# diagramm.net
KiCad netlist of a schematic drawn in EAGLE
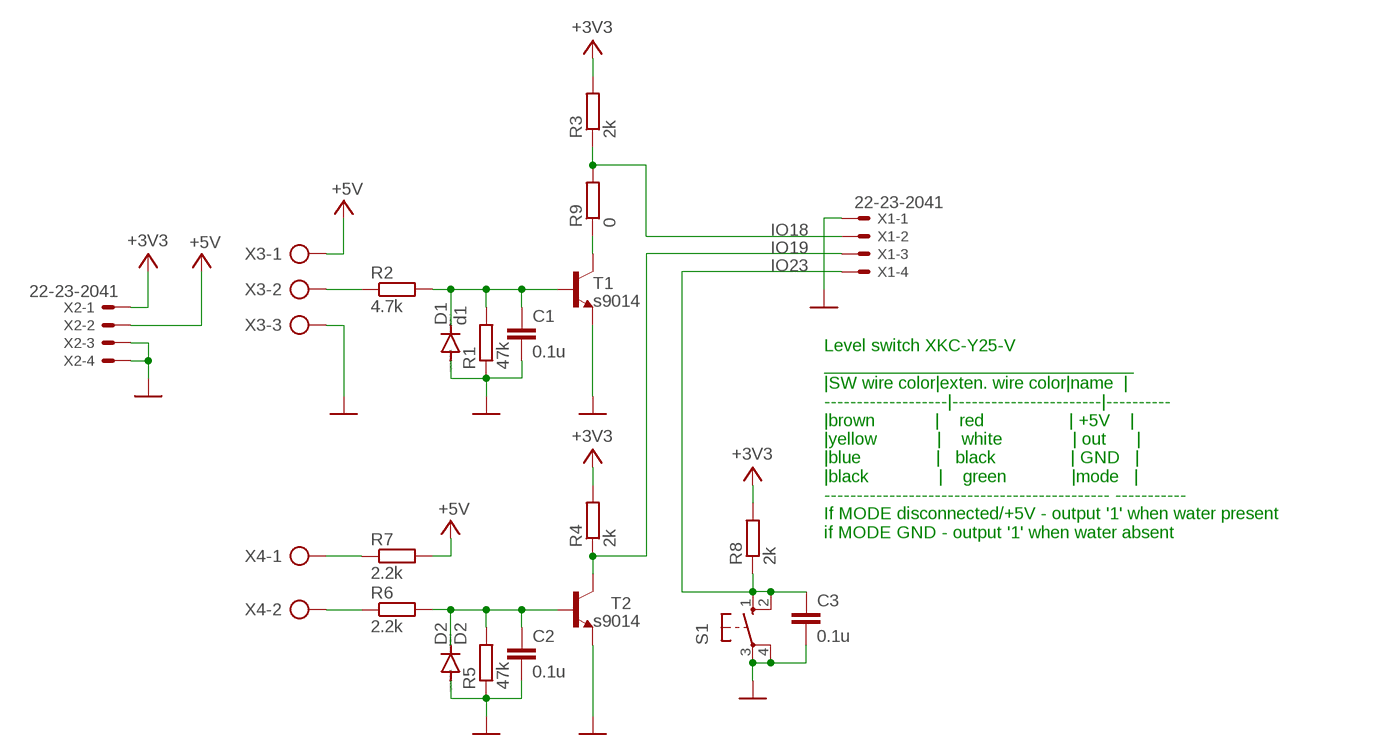
[diagram p0: schematic, sheet 1]

(export (version "E")
  (design (tool "Eeschema 10.0.6"))
  (components
    (comp (ref "C1")
      (value "0.1u")
      (footprint "eagle-import:C1206")
      (libsource (lib "eagle-import") (part "C-EUC1206"))
    )
    (comp (ref "C2")
      (value "0.1u")
      (footprint "eagle-import:C1206")
      (libsource (lib "eagle-import") (part "C-EUC1206"))
    )
    (comp (ref "C3")
      (value "0.1u")
      (footprint "eagle-import:C1206")
      (libsource (lib "eagle-import") (part "C-EUC1206"))
    )
    (comp (ref "D1")
      (value "d1")
      (footprint "eagle-import:DO214AC")
      (libsource (lib "eagle-import") (part "DIODE-DO214AC"))
    )
    (comp (ref "D2")
      (value "D2")
      (footprint "eagle-import:DO214AC")
      (libsource (lib "eagle-import") (part "DIODE-DO214AC"))
    )
    (comp (ref "R1")
      (value "47k")
      (footprint "eagle-import:R1206")
      (libsource (lib "eagle-import") (part "R-EU_R1206"))
    )
    (comp (ref "R2")
      (value "4.7k")
      (footprint "eagle-import:R1206")
      (libsource (lib "eagle-import") (part "R-EU_R1206"))
    )
    (comp (ref "R3")
      (value "2k")
      (footprint "eagle-import:R1206")
      (libsource (lib "eagle-import") (part "R-EU_R1206"))
    )
    (comp (ref "R4")
      (value "2k")
      (footprint "eagle-import:R1206")
      (libsource (lib "eagle-import") (part "R-EU_R1206"))
    )
    (comp (ref "R5")
      (value "47k")
      (footprint "eagle-import:R1206")
      (libsource (lib "eagle-import") (part "R-EU_R1206"))
    )
    (comp (ref "R6")
      (value "2.2k")
      (footprint "eagle-import:R1206")
      (libsource (lib "eagle-import") (part "R-EU_R1206"))
    )
    (comp (ref "R7")
      (value "2.2k")
      (footprint "eagle-import:R1206")
      (libsource (lib "eagle-import") (part "R-EU_R1206"))
    )
    (comp (ref "R8")
      (value "2k")
      (footprint "eagle-import:R1206")
      (libsource (lib "eagle-import") (part "R-EU_R1206"))
    )
    (comp (ref "R9")
      (value "0")
      (footprint "eagle-import:R1206")
      (libsource (lib "eagle-import") (part "R-EU_R1206"))
    )
    (comp (ref "S1")
      (value "10-XX")
      (footprint "eagle-import:B3F-10XX")
      (fields (field (name "MPN") "B3F-1000"))
      (libsource (lib "eagle-import") (part "10-XX"))
    )
    (comp (ref "T1")
      (value "s9014")
      (footprint "eagle-import:SOT23-BEC")
      (libsource (lib "eagle-import") (part "-NPN-SOT23-BECBC808"))
    )
    (comp (ref "T2")
      (value "s9014")
      (footprint "eagle-import:SOT23-BEC")
      (libsource (lib "eagle-import") (part "-NPN-SOT23-BECBC808"))
    )
    (comp (ref "X1")
      (value "22-23-2041")
      (footprint "eagle-import:22-23-2041")
      (fields (field (name "MF") "MOLEX"))
      (libsource (lib "eagle-import") (part "22-23-2041"))
    )
    (comp (ref "X2")
      (value "22-23-2041")
      (footprint "eagle-import:22-23-2041")
      (fields (field (name "MF") "MOLEX"))
      (libsource (lib "eagle-import") (part "22-23-2041"))
    )
    (comp (ref "X3")
      (value "AK300/3")
      (footprint "eagle-import:AK300_3")
      (libsource (lib "eagle-import") (part "AK300/3"))
    )
    (comp (ref "X4")
      (value "AK300/2")
      (footprint "eagle-import:AK300_2")
      (libsource (lib "eagle-import") (part "AK300/2"))
    )
  )
  (nets
    (net (code "1") (name "+3V3") (class "Default")
      (node (ref "R3") (pin "2") (pinfunction "2_2") (pintype "passive"))
      (node (ref "R4") (pin "2") (pinfunction "2_2") (pintype "passive"))
      (node (ref "R8") (pin "2") (pinfunction "2_2") (pintype "passive"))
      (node (ref "X2") (pin "1") (pinfunction "S_1") (pintype "passive"))
    )
    (net (code "2") (name "+5V") (class "Default")
      (node (ref "R7") (pin "2") (pinfunction "2_2") (pintype "passive"))
      (node (ref "X2") (pin "2") (pinfunction "S_2") (pintype "passive"))
      (node (ref "X3") (pin "1") (pinfunction "KL_1") (pintype "passive"))
    )
    (net (code "3") (name "/IO18") (class "Default")
      (node (ref "R3") (pin "1") (pinfunction "1_1") (pintype "passive"))
      (node (ref "R9") (pin "2") (pinfunction "2_2") (pintype "passive"))
      (node (ref "X1") (pin "2") (pinfunction "S_2") (pintype "passive"))
    )
    (net (code "4") (name "/IO19") (class "Default")
      (node (ref "R4") (pin "1") (pinfunction "1_1") (pintype "passive"))
      (node (ref "T2") (pin "C") (pinfunction "C_C") (pintype "passive"))
      (node (ref "X1") (pin "3") (pinfunction "S_3") (pintype "passive"))
    )
    (net (code "5") (name "/IO23") (class "Default")
      (node (ref "C3") (pin "1") (pinfunction "1_1") (pintype "passive"))
      (node (ref "R8") (pin "1") (pinfunction "1_1") (pintype "passive"))
      (node (ref "S1") (pin "1") (pinfunction "S_1") (pintype "passive"))
      (node (ref "S1") (pin "2") (pinfunction "S1_2") (pintype "passive"))
      (node (ref "X1") (pin "4") (pinfunction "S_4") (pintype "passive"))
    )
    (net (code "6") (name "GND") (class "Default")
      (node (ref "C1") (pin "2") (pinfunction "2_2") (pintype "passive"))
      (node (ref "C2") (pin "2") (pinfunction "2_2") (pintype "passive"))
      (node (ref "C3") (pin "2") (pinfunction "2_2") (pintype "passive"))
      (node (ref "D1") (pin "A") (pinfunction "A_A") (pintype "passive"))
      (node (ref "D2") (pin "A") (pinfunction "A_A") (pintype "passive"))
      (node (ref "R1") (pin "1") (pinfunction "1_1") (pintype "passive"))
      (node (ref "R5") (pin "1") (pinfunction "1_1") (pintype "passive"))
      (node (ref "S1") (pin "3") (pinfunction "P_3") (pintype "passive"))
      (node (ref "S1") (pin "4") (pinfunction "P1_4") (pintype "passive"))
      (node (ref "T1") (pin "E") (pinfunction "E_E") (pintype "passive"))
      (node (ref "T2") (pin "E") (pinfunction "E_E") (pintype "passive"))
      (node (ref "X1") (pin "1") (pinfunction "S_1") (pintype "passive"))
      (node (ref "X2") (pin "3") (pinfunction "S_3") (pintype "passive"))
      (node (ref "X2") (pin "4") (pinfunction "S_4") (pintype "passive"))
      (node (ref "X3") (pin "3") (pinfunction "KL_3") (pintype "passive"))
    )
    (net (code "7") (name "Net-(C1-Pad1)") (class "Default")
      (node (ref "C1") (pin "1") (pinfunction "1_1") (pintype "passive"))
      (node (ref "D1") (pin "C") (pinfunction "C_C") (pintype "passive"))
      (node (ref "R1") (pin "2") (pinfunction "2_2") (pintype "passive"))
      (node (ref "R2") (pin "2") (pinfunction "2_2") (pintype "passive"))
      (node (ref "T1") (pin "B") (pinfunction "B_B") (pintype "passive"))
    )
    (net (code "8") (name "Net-(C2-Pad1)") (class "Default")
      (node (ref "C2") (pin "1") (pinfunction "1_1") (pintype "passive"))
      (node (ref "D2") (pin "C") (pinfunction "C_C") (pintype "passive"))
      (node (ref "R5") (pin "2") (pinfunction "2_2") (pintype "passive"))
      (node (ref "R6") (pin "2") (pinfunction "2_2") (pintype "passive"))
      (node (ref "T2") (pin "B") (pinfunction "B_B") (pintype "passive"))
    )
    (net (code "9") (name "Net-(R9-Pad1)") (class "Default")
      (node (ref "R9") (pin "1") (pinfunction "1_1") (pintype "passive"))
      (node (ref "T1") (pin "C") (pinfunction "C_C") (pintype "passive"))
    )
    (net (code "10") (name "Net-(X3B-KL)") (class "Default")
      (node (ref "R2") (pin "1") (pinfunction "1_1") (pintype "passive"))
      (node (ref "X3") (pin "2") (pinfunction "KL_2") (pintype "passive"))
    )
    (net (code "11") (name "Net-(X4A-KL)") (class "Default")
      (node (ref "R7") (pin "1") (pinfunction "1_1") (pintype "passive"))
      (node (ref "X4") (pin "1") (pinfunction "KL_1") (pintype "passive"))
    )
    (net (code "12") (name "Net-(X4B-KL)") (class "Default")
      (node (ref "R6") (pin "1") (pinfunction "1_1") (pintype "passive"))
      (node (ref "X4") (pin "2") (pinfunction "KL_2") (pintype "passive"))
    )
  )
)
